# V_reduction_module.net
KiCad netlist of a schematic drawn in EasyEDA Pro
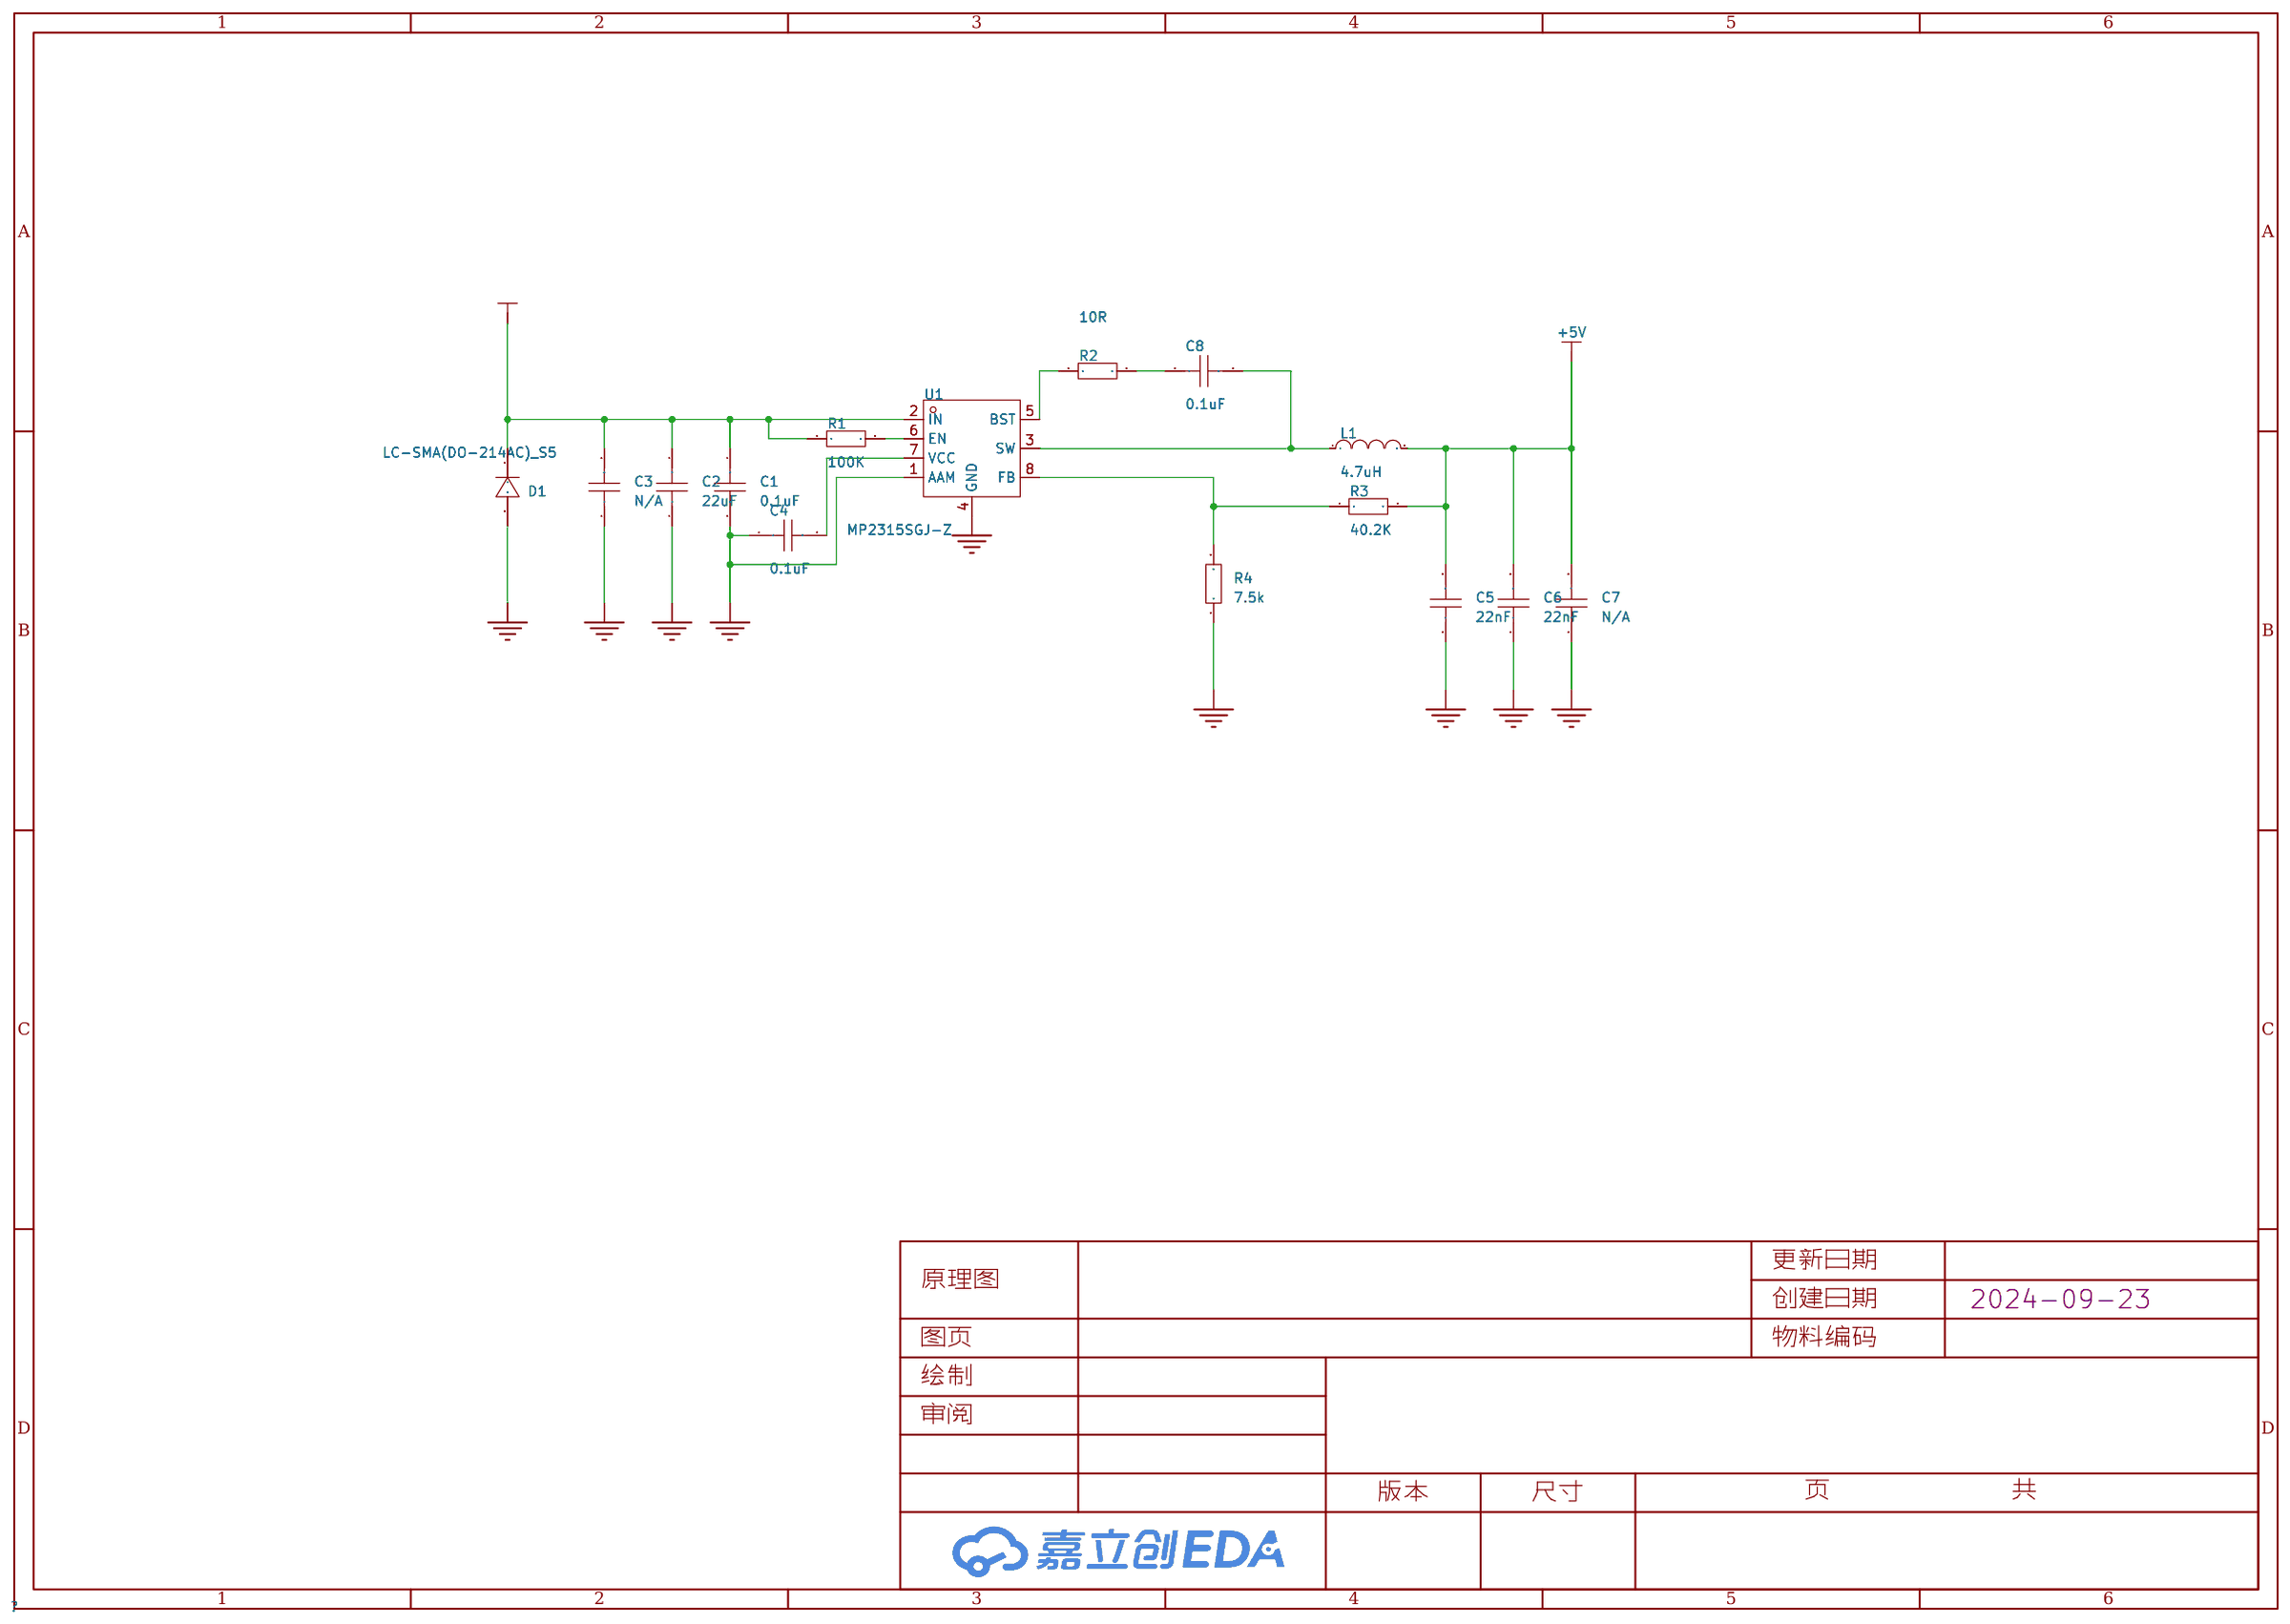
[diagram p0: schematic sheet]

(export (version "E")
  (design (tool "Eeschema 10.0.6"))
  (components
    (comp (ref "C1")
      (value "22uF")
      (footprint "easyedapro:C1210")
      (description "容值:22uF;精度:±20%;额定电压:35V;材质(温度系数):X5R;")
      (fields
        (field (name "Manufacturer Part") "HGC1210R5226M350NSVK")
        (field (name "Manufacturer") "Chinocera(华瓷)")
      )
      (libsource (lib "easyedapro") (part "HGC1210R5226M350NSVK"))
    )
    (comp (ref "C2")
      (value "22uF")
      (footprint "easyedapro:C0603")
      (libsource (lib "easyedapro") (part "CapAcitance"))
    )
    (comp (ref "C3")
      (value "100nF")
      (footprint "easyedapro:C0603")
      (libsource (lib "easyedapro") (part "CapAcitance"))
    )
    (comp (ref "C4")
      (value "0.1uF")
      (footprint "easyedapro:C0603")
      (libsource (lib "easyedapro") (part "CapAcitance"))
    )
    (comp (ref "C5")
      (value "22nF")
      (footprint "easyedapro:C0603")
      (libsource (lib "easyedapro") (part "CapAcitance"))
    )
    (comp (ref "C6")
      (value "22nF")
      (footprint "easyedapro:C0603")
      (libsource (lib "easyedapro") (part "CapAcitance"))
    )
    (comp (ref "C7")
      (value "N/A")
      (footprint "easyedapro:C0603")
      (libsource (lib "easyedapro") (part "CapAcitance"))
    )
    (comp (ref "C8")
      (value "0.1uF")
      (footprint "easyedapro:C0603")
      (libsource (lib "easyedapro") (part "CapAcitance"))
    )
    (comp (ref "D1")
      (value "LC-SMA(DO-214AC)_S5")
      (footprint "easyedapro:SMA_L4.3-W2.7-LS5.1-RD")
      (libsource (lib "easyedapro") (part "LC-SMA(DO-214AC)_S5"))
    )
    (comp (ref "L1")
      (value "4.7uH")
      (footprint "easyedapro:L0603")
      (libsource (lib "easyedapro") (part "SDFL1608S100KTF"))
    )
    (comp (ref "R1") (value "10K") (footprint "easyedapro:R0603") (libsource (lib "easyedapro") (part "电阻")))
    (comp (ref "R2") (value "10R") (footprint "easyedapro:R0603") (libsource (lib "easyedapro") (part "电阻")))
    (comp (ref "R3")
      (value "40.2K")
      (footprint "easyedapro:R0603")
      (libsource (lib "easyedapro") (part "电阻"))
    )
    (comp (ref "R4") (value "7.5k") (footprint "easyedapro:R0603") (libsource (lib "easyedapro") (part "电阻")))
    (comp (ref "U1")
      (value "MP2315SGJ-Z")
      (footprint "easyedapro:TSOT-23-8_L2.9-W1.6-P0.65-LS2.8-BL")
      (description "功能类型:降压型;输出类型:可调;输入电压:4.5V~24V;输出电压:800mV~22.8V;输出电流:3A;")
      (fields (field (name "Manufacturer") "MPS(芯源)"))
      (libsource (lib "easyedapro") (part "MP2315SGJ-Z"))
    )
  )
  (nets
    (net (code "1") (name "+5V") (class "Default")
      (node (ref "C5") (pin "2") (pinfunction "2_2") (pintype "input"))
      (node (ref "C6") (pin "2") (pinfunction "2_2") (pintype "input"))
      (node (ref "C7") (pin "2") (pinfunction "2_2") (pintype "input"))
      (node (ref "L1") (pin "2") (pinfunction "2_2") (pintype "unspecified"))
      (node (ref "R3") (pin "2") (pinfunction "2_2") (pintype "input"))
    )
    (net (code "2") (name "+24V") (class "Default")
      (node (ref "C1") (pin "1") (pinfunction "1_1") (pintype "unspecified"))
      (node (ref "C2") (pin "2") (pinfunction "2_2") (pintype "input"))
      (node (ref "C3") (pin "2") (pinfunction "2_2") (pintype "input"))
      (node (ref "D1") (pin "1") (pinfunction "1_1") (pintype "unspecified"))
      (node (ref "R1") (pin "1") (pinfunction "1_1") (pintype "input"))
      (node (ref "U1") (pin "2") (pinfunction "IN_2") (pintype "unspecified"))
    )
    (net (code "3") (name "GND") (class "Default")
      (node (ref "C1") (pin "2") (pinfunction "2_2") (pintype "unspecified"))
      (node (ref "C2") (pin "1") (pinfunction "1_1") (pintype "input"))
      (node (ref "C3") (pin "1") (pinfunction "1_1") (pintype "input"))
      (node (ref "C4") (pin "1") (pinfunction "1_1") (pintype "input"))
      (node (ref "C5") (pin "1") (pinfunction "1_1") (pintype "input"))
      (node (ref "C6") (pin "1") (pinfunction "1_1") (pintype "input"))
      (node (ref "C7") (pin "1") (pinfunction "1_1") (pintype "input"))
      (node (ref "D1") (pin "2") (pinfunction "2_2") (pintype "unspecified"))
      (node (ref "R4") (pin "1") (pinfunction "1_1") (pintype "input"))
      (node (ref "U1") (pin "1") (pinfunction "AAM_1") (pintype "unspecified"))
      (node (ref "U1") (pin "4") (pinfunction "GND_4") (pintype "unspecified"))
    )
    (net (code "4") (name "Net-(C8-Pad1)") (class "Default")
      (node (ref "C8") (pin "1") (pinfunction "1_1") (pintype "input"))
      (node (ref "R2") (pin "2") (pinfunction "2_2") (pintype "input"))
    )
    (net (code "5") (name "Net-(U1-BST)") (class "Default")
      (node (ref "R2") (pin "1") (pinfunction "1_1") (pintype "input"))
      (node (ref "U1") (pin "5") (pinfunction "BST_5") (pintype "unspecified"))
    )
    (net (code "6") (name "Net-(U1-EN)") (class "Default")
      (node (ref "R1") (pin "2") (pinfunction "2_2") (pintype "input"))
      (node (ref "U1") (pin "6") (pinfunction "EN_6") (pintype "unspecified"))
    )
    (net (code "7") (name "Net-(U1-FB)") (class "Default")
      (node (ref "R3") (pin "1") (pinfunction "1_1") (pintype "input"))
      (node (ref "R4") (pin "2") (pinfunction "2_2") (pintype "input"))
      (node (ref "U1") (pin "8") (pinfunction "FB_8") (pintype "unspecified"))
    )
    (net (code "8") (name "Net-(U1-SW)") (class "Default")
      (node (ref "C8") (pin "2") (pinfunction "2_2") (pintype "input"))
      (node (ref "L1") (pin "1") (pinfunction "1_1") (pintype "unspecified"))
      (node (ref "U1") (pin "3") (pinfunction "SW_3") (pintype "unspecified"))
    )
    (net (code "9") (name "Net-(U1-VCC)") (class "Default")
      (node (ref "C4") (pin "2") (pinfunction "2_2") (pintype "input"))
      (node (ref "U1") (pin "7") (pinfunction "VCC_7") (pintype "unspecified"))
    )
  )
)
